# rs485.net
KiCad netlist of a schematic drawn in Altium Designer
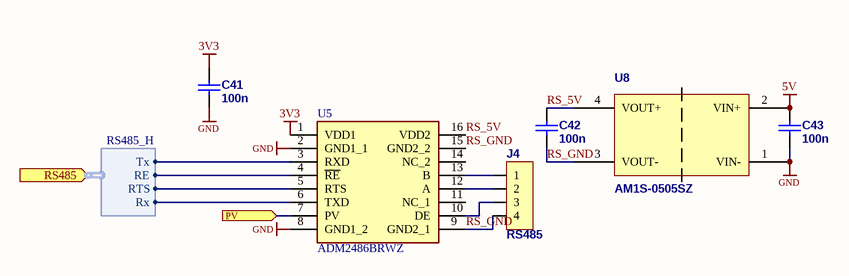
[diagram p0: rs485.SchDoc]

(export (version "E")
  (design (tool "Eeschema 10.0.6"))
  (components
    (comp (ref "C41")
      (value "100n")
      (footprint "C0805")
      (description "Capacitor")
      (libsource (lib "capacitors") (part "Cap"))
    )
    (comp (ref "C42")
      (value "100n")
      (footprint "C0805")
      (description "Capacitor")
      (libsource (lib "capacitors") (part "Cap"))
    )
    (comp (ref "C43")
      (value "100n")
      (footprint "C0805")
      (description "Capacitor")
      (libsource (lib "capacitors") (part "Cap"))
    )
    (comp (ref "J4")
      (value "RS485")
      (footprint "15EDGRC-3.81/4P_WO_CN")
      (description "Degson 20A, 320V, 4 Pole Plug-in Terminal Block")
      (libsource (lib "terminal_blocks") (part "2EDGVC-5.0-4P"))
    )
    (comp (ref "U5")
      (value "ADM2486BRWZ")
      (footprint "SamacSys:SOIC127P1032X265-16N")
      (description "Integrated Circuit")
      (fields (field (name "MOUSER PART NUMBER") "584-ADM2486BRWZ"))
      (libsource (lib "*") (part "ADM2486BRWZ"))
    )
    (comp (ref "U8")
      (value "AM1S-0505SZ")
      (footprint "AM1S-Z")
      (description "Aimtec 1Watt DC/DC Converter: 5V Input, 5V@200mA Output")
      (libsource (lib "dc_dc_converters") (part "AM1S-0505SZ"))
    )
  )
  (nets
    (net (code "2") (name "/PV") (class "Default")
      (node (ref "U5") (pin "7") (pinfunction "PV_7") (pintype "passive"))
    )
    (net (code "3") (name "/RE") (class "Default")
      (node (ref "U5") (pin "4") (pinfunction "~{RE}_4") (pintype "passive"))
    )
    (net (code "4") (name "/RS_5V") (class "Default")
      (node (ref "C42") (pin "2") (pinfunction "2_2") (pintype "passive"))
      (node (ref "U5") (pin "16") (pinfunction "VDD2_16") (pintype "passive"))
      (node (ref "U8") (pin "4") (pinfunction "VOUT+_4") (pintype "power_in"))
    )
    (net (code "5") (name "/RS_GND") (class "Default")
      (node (ref "C42") (pin "1") (pinfunction "1_1") (pintype "passive"))
      (node (ref "J4") (pin "4") (pinfunction "4_4") (pintype "passive"))
      (node (ref "U5") (pin "15") (pinfunction "GND2_2_15") (pintype "passive"))
      (node (ref "U5") (pin "9") (pinfunction "GND2_1_9") (pintype "passive"))
      (node (ref "U8") (pin "3") (pinfunction "VOUT-_3") (pintype "power_in"))
    )
    (net (code "6") (name "/RTS") (class "Default")
      (node (ref "U5") (pin "5") (pinfunction "RTS_5") (pintype "passive"))
    )
    (net (code "7") (name "/Rx") (class "Default")
      (node (ref "U5") (pin "6") (pinfunction "TXD_6") (pintype "passive"))
    )
    (net (code "8") (name "/Tx") (class "Default")
      (node (ref "U5") (pin "3") (pinfunction "RXD_3") (pintype "passive"))
    )
    (net (code "10") (name "3V3") (class "Default")
      (node (ref "C41") (pin "2") (pinfunction "2_2") (pintype "passive"))
      (node (ref "U5") (pin "1") (pinfunction "VDD1_1") (pintype "passive"))
    )
    (net (code "11") (name "5V") (class "Default")
      (node (ref "C43") (pin "1") (pinfunction "1_1") (pintype "passive"))
      (node (ref "U8") (pin "2") (pinfunction "VIN+_2") (pintype "power_in"))
    )
    (net (code "12") (name "GND") (class "Default")
      (node (ref "C41") (pin "1") (pinfunction "1_1") (pintype "passive"))
      (node (ref "C43") (pin "2") (pinfunction "2_2") (pintype "passive"))
      (node (ref "U5") (pin "2") (pinfunction "GND1_1_2") (pintype "passive"))
      (node (ref "U5") (pin "8") (pinfunction "GND1_2_8") (pintype "passive"))
      (node (ref "U8") (pin "1") (pinfunction "VIN-_1") (pintype "power_in"))
    )
    (net (code "13") (name "Net-(U5-A)") (class "Default")
      (node (ref "J4") (pin "2") (pinfunction "2_2") (pintype "passive"))
      (node (ref "U5") (pin "12") (pinfunction "A_12") (pintype "passive"))
    )
    (net (code "14") (name "Net-(U5-B)") (class "Default")
      (node (ref "J4") (pin "1") (pinfunction "1_1") (pintype "passive"))
      (node (ref "U5") (pin "13") (pinfunction "B_13") (pintype "passive"))
    )
    (net (code "15") (name "Net-(U5-DE)") (class "Default")
      (node (ref "J4") (pin "3") (pinfunction "3_3") (pintype "passive"))
      (node (ref "U5") (pin "10") (pinfunction "DE_10") (pintype "passive"))
    )
    (net (code "16") (name "unconnected-(U5-NC_1-Pad11)") (class "Default")
      (node (ref "U5") (pin "11") (pinfunction "NC_1_11") (pintype "passive"))
    )
    (net (code "17") (name "unconnected-(U5-NC_2-Pad14)") (class "Default")
      (node (ref "U5") (pin "14") (pinfunction "NC_2_14") (pintype "passive"))
    )
  )
)
